# Pin-with-a-screen.net
KiCad netlist of a schematic drawn in EAGLE
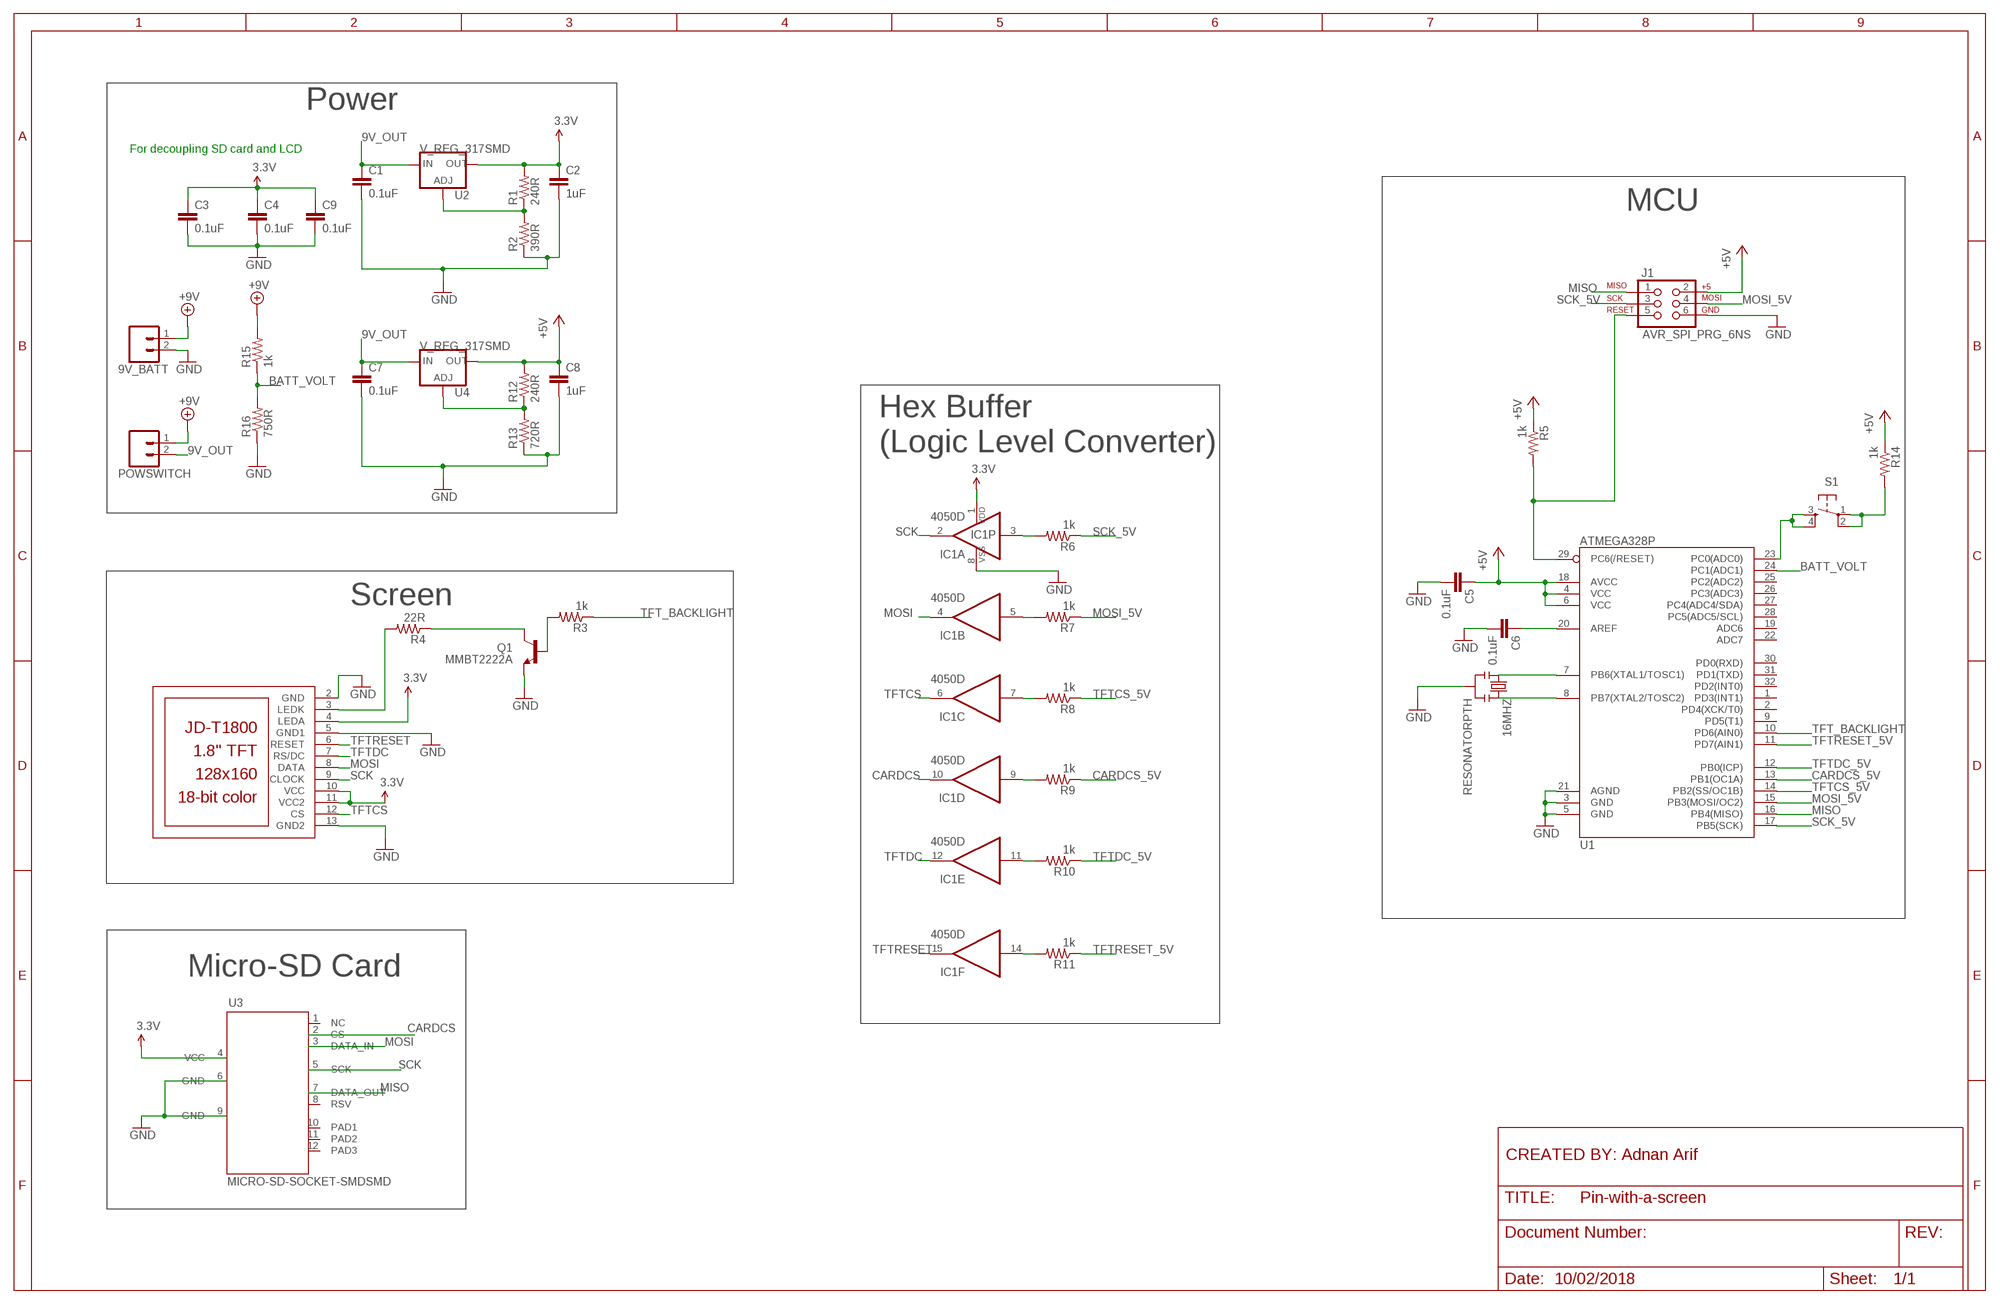
[diagram p0: schematic, sheet 1]

(export (version "E")
  (design (tool "Eeschema 10.0.6"))
  (components
    (comp (ref "9V_BATT")
      (value "M02POGO_PIN_HOLES_ONLY")
      (footprint "eagle-import:1X02_PP_HOLES_ONLY")
      (libsource (lib "eagle-import") (part "M02POGO_PIN_HOLES_ONLY"))
    )
    (comp (ref "16MHZ")
      (value "RESONATORPTH")
      (footprint "eagle-import:RESONATOR-PTH")
      (libsource (lib "eagle-import") (part "RESONATORPTH"))
    )
    (comp (ref "C1")
      (value "0.1uF")
      (footprint "eagle-import:0603-CAP")
      (libsource (lib "eagle-import") (part "CAP0603-CAP"))
    )
    (comp (ref "C2")
      (value "1uF")
      (footprint "eagle-import:0603-CAP")
      (libsource (lib "eagle-import") (part "CAP0603-CAP"))
    )
    (comp (ref "C3")
      (value "0.1uF")
      (footprint "eagle-import:0603-CAP")
      (libsource (lib "eagle-import") (part "CAP0603-CAP"))
    )
    (comp (ref "C4")
      (value "0.1uF")
      (footprint "eagle-import:0603-CAP")
      (libsource (lib "eagle-import") (part "CAP0603-CAP"))
    )
    (comp (ref "C5")
      (value "0.1uF")
      (footprint "eagle-import:0603-CAP")
      (libsource (lib "eagle-import") (part "CAP0603-CAP"))
    )
    (comp (ref "C6")
      (value "0.1uF")
      (footprint "eagle-import:0603-CAP")
      (libsource (lib "eagle-import") (part "CAP0603-CAP"))
    )
    (comp (ref "C7")
      (value "0.1uF")
      (footprint "eagle-import:0603-CAP")
      (libsource (lib "eagle-import") (part "CAP0603-CAP"))
    )
    (comp (ref "C8")
      (value "1uF")
      (footprint "eagle-import:0603-CAP")
      (libsource (lib "eagle-import") (part "CAP0603-CAP"))
    )
    (comp (ref "C9")
      (value "0.1uF")
      (footprint "eagle-import:0603-CAP")
      (libsource (lib "eagle-import") (part "CAP0603-CAP"))
    )
    (comp (ref "IC1")
      (value "4050D")
      (footprint "eagle-import:SO16")
      (libsource (lib "eagle-import") (part "4050D"))
    )
    (comp (ref "J1")
      (value "AVR_SPI_PRG_6NS")
      (footprint "eagle-import:2X3-NS")
      (libsource (lib "eagle-import") (part "AVR_SPI_PRG_6NS"))
    )
    (comp (ref "LCD2")
      (value "JD-T1800")
      (footprint "eagle-import:JD-T1800")
      (libsource (lib "eagle-import") (part "JD-T1800"))
    )
    (comp (ref "POWSWITCH")
      (value "M02POGO_PIN_HOLES_ONLY")
      (footprint "eagle-import:1X02_PP_HOLES_ONLY")
      (libsource (lib "eagle-import") (part "M02POGO_PIN_HOLES_ONLY"))
    )
    (comp (ref "Q1")
      (value "MMBT2222A")
      (footprint "eagle-import:SOT23-3")
      (libsource (lib "eagle-import") (part "TRANSISTOR_NPNMMBT2222A"))
    )
    (comp (ref "R1")
      (value "240R")
      (footprint "eagle-import:0603-RES")
      (libsource (lib "eagle-import") (part "RESISTOR0603-RES"))
    )
    (comp (ref "R2")
      (value "390R")
      (footprint "eagle-import:0603-RES")
      (libsource (lib "eagle-import") (part "RESISTOR0603-RES"))
    )
    (comp (ref "R3")
      (value "1k")
      (footprint "eagle-import:0603-RES")
      (libsource (lib "eagle-import") (part "RESISTOR0603-RES"))
    )
    (comp (ref "R4")
      (value "22R")
      (footprint "eagle-import:0603-RES")
      (libsource (lib "eagle-import") (part "RESISTOR0603-RES"))
    )
    (comp (ref "R5")
      (value "1k")
      (footprint "eagle-import:0603-RES")
      (libsource (lib "eagle-import") (part "RESISTOR0603-RES"))
    )
    (comp (ref "R6")
      (value "1k")
      (footprint "eagle-import:0603-RES")
      (libsource (lib "eagle-import") (part "RESISTOR0603-RES"))
    )
    (comp (ref "R7")
      (value "1k")
      (footprint "eagle-import:0603-RES")
      (libsource (lib "eagle-import") (part "RESISTOR0603-RES"))
    )
    (comp (ref "R8")
      (value "1k")
      (footprint "eagle-import:0603-RES")
      (libsource (lib "eagle-import") (part "RESISTOR0603-RES"))
    )
    (comp (ref "R9")
      (value "1k")
      (footprint "eagle-import:0603-RES")
      (libsource (lib "eagle-import") (part "RESISTOR0603-RES"))
    )
    (comp (ref "R10")
      (value "1k")
      (footprint "eagle-import:0603-RES")
      (libsource (lib "eagle-import") (part "RESISTOR0603-RES"))
    )
    (comp (ref "R11")
      (value "1k")
      (footprint "eagle-import:0603-RES")
      (libsource (lib "eagle-import") (part "RESISTOR0603-RES"))
    )
    (comp (ref "R12")
      (value "240R")
      (footprint "eagle-import:0603-RES")
      (libsource (lib "eagle-import") (part "RESISTOR0603-RES"))
    )
    (comp (ref "R13")
      (value "720R")
      (footprint "eagle-import:0603-RES")
      (libsource (lib "eagle-import") (part "RESISTOR0603-RES"))
    )
    (comp (ref "R14")
      (value "1k")
      (footprint "eagle-import:0603-RES")
      (libsource (lib "eagle-import") (part "RESISTOR0603-RES"))
    )
    (comp (ref "R15")
      (value "1k")
      (footprint "eagle-import:0603-RES")
      (libsource (lib "eagle-import") (part "RESISTOR0603-RES"))
    )
    (comp (ref "R16")
      (value "750R")
      (footprint "eagle-import:0603-RES")
      (libsource (lib "eagle-import") (part "RESISTOR0603-RES"))
    )
    (comp (ref "S1")
      (value "TAC_SWITCHPTH")
      (footprint "eagle-import:TACTILE-PTH")
      (libsource (lib "eagle-import") (part "TAC_SWITCHPTH"))
    )
    (comp (ref "U1")
      (value "ATMEGA328P")
      (footprint "eagle-import:TQFP32-08")
      (libsource (lib "eagle-import") (part "ATMEGA328_SMT"))
    )
    (comp (ref "U2")
      (value "V_REG_317SMD")
      (footprint "eagle-import:SOT223")
      (libsource (lib "eagle-import") (part "V_REG_317SMD"))
    )
    (comp (ref "U3")
      (value "MICRO-SD-SOCKET-SMDSMD")
      (footprint "eagle-import:MICRO-SD-SOCKET-SMD")
      (libsource (lib "eagle-import") (part "MICRO-SD-SOCKET-SMDSMD"))
    )
    (comp (ref "U4")
      (value "V_REG_317SMD")
      (footprint "eagle-import:SOT223")
      (libsource (lib "eagle-import") (part "V_REG_317SMD"))
    )
  )
  (nets
    (net (code "1") (name "+5V") (class "Default")
      (node (ref "C5") (pin "1") (pinfunction "1_1") (pintype "passive"))
      (node (ref "C8") (pin "1") (pinfunction "1_1") (pintype "passive"))
      (node (ref "J1") (pin "2") (pinfunction "2_2") (pintype "passive"))
      (node (ref "R12") (pin "2") (pinfunction "2_2") (pintype "passive"))
      (node (ref "R14") (pin "1") (pinfunction "1_1") (pintype "passive"))
      (node (ref "R5") (pin "1") (pinfunction "1_1") (pintype "passive"))
      (node (ref "U1") (pin "18") (pinfunction "AVCC_18") (pintype "bidirectional"))
      (node (ref "U1") (pin "4") (pinfunction "VCC_4") (pintype "bidirectional"))
      (node (ref "U1") (pin "6") (pinfunction "VCC_6") (pintype "bidirectional"))
      (node (ref "U4") (pin "2") (pinfunction "OUT_2") (pintype "output"))
    )
    (net (code "2") (name "+9V") (class "Default")
      (node (ref "9V_BATT") (pin "1") (pinfunction "1_1") (pintype "passive"))
      (node (ref "POWSWITCH") (pin "1") (pinfunction "1_1") (pintype "passive"))
      (node (ref "R15") (pin "2") (pinfunction "2_2") (pintype "passive"))
    )
    (net (code "3") (name "/9V_OUT") (class "Default")
      (node (ref "C1") (pin "1") (pinfunction "1_1") (pintype "passive"))
      (node (ref "C7") (pin "1") (pinfunction "1_1") (pintype "passive"))
      (node (ref "POWSWITCH") (pin "2") (pinfunction "2_2") (pintype "passive"))
      (node (ref "U2") (pin "3") (pinfunction "IN_3") (pintype "input"))
      (node (ref "U4") (pin "3") (pinfunction "IN_3") (pintype "input"))
    )
    (net (code "4") (name "/BATT_VOLT") (class "Default")
      (node (ref "R15") (pin "1") (pinfunction "1_1") (pintype "passive"))
      (node (ref "R16") (pin "2") (pinfunction "2_2") (pintype "passive"))
      (node (ref "U1") (pin "24") (pinfunction "PC1(ADC1)_24") (pintype "bidirectional"))
    )
    (net (code "5") (name "/CARDCS") (class "Default")
      (node (ref "IC1") (pin "10") (pinfunction "O_10") (pintype "output"))
      (node (ref "U3") (pin "2") (pinfunction "CS_2") (pintype "input"))
    )
    (net (code "6") (name "/CARDCS_5V") (class "Default")
      (node (ref "R9") (pin "1") (pinfunction "1_1") (pintype "passive"))
      (node (ref "U1") (pin "13") (pinfunction "PB1(OC1A)_13") (pintype "bidirectional"))
    )
    (net (code "7") (name "/MISO") (class "Default")
      (node (ref "J1") (pin "1") (pinfunction "1_1") (pintype "passive"))
      (node (ref "U1") (pin "16") (pinfunction "PB4(MISO)_16") (pintype "bidirectional"))
      (node (ref "U3") (pin "7") (pinfunction "DATA_OUT_7") (pintype "output"))
    )
    (net (code "8") (name "/MOSI") (class "Default")
      (node (ref "IC1") (pin "4") (pinfunction "O_4") (pintype "output"))
      (node (ref "LCD2") (pin "8") (pinfunction "DATA_8") (pintype "bidirectional"))
      (node (ref "U3") (pin "3") (pinfunction "DATA_IN_3") (pintype "input"))
    )
    (net (code "9") (name "/MOSI_5V") (class "Default")
      (node (ref "J1") (pin "4") (pinfunction "4_4") (pintype "passive"))
      (node (ref "R7") (pin "1") (pinfunction "1_1") (pintype "passive"))
      (node (ref "U1") (pin "15") (pinfunction "PB3(MOSI/OC2)_15") (pintype "bidirectional"))
    )
    (net (code "10") (name "/SCK") (class "Default")
      (node (ref "IC1") (pin "2") (pinfunction "O_2") (pintype "output"))
      (node (ref "LCD2") (pin "9") (pinfunction "CLOCK_9") (pintype "input"))
      (node (ref "U3") (pin "5") (pinfunction "SCK_5") (pintype "input"))
    )
    (net (code "11") (name "/SCK_5V") (class "Default")
      (node (ref "J1") (pin "3") (pinfunction "3_3") (pintype "passive"))
      (node (ref "R6") (pin "1") (pinfunction "1_1") (pintype "passive"))
      (node (ref "U1") (pin "17") (pinfunction "PB5(SCK)_17") (pintype "bidirectional"))
    )
    (net (code "12") (name "/TFTCS") (class "Default")
      (node (ref "IC1") (pin "6") (pinfunction "O_6") (pintype "output"))
      (node (ref "LCD2") (pin "12") (pinfunction "CS_12") (pintype "input"))
    )
    (net (code "13") (name "/TFTCS_5V") (class "Default")
      (node (ref "R8") (pin "1") (pinfunction "1_1") (pintype "passive"))
      (node (ref "U1") (pin "14") (pinfunction "PB2(SS/OC1B)_14") (pintype "bidirectional"))
    )
    (net (code "14") (name "/TFTDC") (class "Default")
      (node (ref "IC1") (pin "12") (pinfunction "O_12") (pintype "output"))
      (node (ref "LCD2") (pin "7") (pinfunction "RS/DC_7") (pintype "input"))
    )
    (net (code "15") (name "/TFTDC_5V") (class "Default")
      (node (ref "R10") (pin "1") (pinfunction "1_1") (pintype "passive"))
      (node (ref "U1") (pin "12") (pinfunction "PB0(ICP)_12") (pintype "bidirectional"))
    )
    (net (code "16") (name "/TFTRESET") (class "Default")
      (node (ref "IC1") (pin "15") (pinfunction "O_15") (pintype "output"))
      (node (ref "LCD2") (pin "6") (pinfunction "RESET_6") (pintype "input"))
    )
    (net (code "17") (name "/TFTRESET_5V") (class "Default")
      (node (ref "R11") (pin "1") (pinfunction "1_1") (pintype "passive"))
      (node (ref "U1") (pin "11") (pinfunction "PD7(AIN1)_11") (pintype "bidirectional"))
    )
    (net (code "18") (name "/TFT_BACKLIGHT") (class "Default")
      (node (ref "R3") (pin "1") (pinfunction "1_1") (pintype "passive"))
      (node (ref "U1") (pin "10") (pinfunction "PD6(AIN0)_10") (pintype "bidirectional"))
    )
    (net (code "19") (name "3.3V") (class "Default")
      (node (ref "C2") (pin "1") (pinfunction "1_1") (pintype "passive"))
      (node (ref "C3") (pin "1") (pinfunction "1_1") (pintype "passive"))
      (node (ref "C4") (pin "1") (pinfunction "1_1") (pintype "passive"))
      (node (ref "C9") (pin "1") (pinfunction "1_1") (pintype "passive"))
      (node (ref "IC1") (pin "1") (pinfunction "VDD_1") (pintype "power_in"))
      (node (ref "LCD2") (pin "10") (pinfunction "VCC_10") (pintype "power_in"))
      (node (ref "LCD2") (pin "11") (pinfunction "VCC2_11") (pintype "power_in"))
      (node (ref "LCD2") (pin "4") (pinfunction "LEDA_4") (pintype "input"))
      (node (ref "R1") (pin "2") (pinfunction "2_2") (pintype "passive"))
      (node (ref "U2") (pin "2") (pinfunction "OUT_2") (pintype "output"))
      (node (ref "U3") (pin "4") (pinfunction "VCC_4") (pintype "power_in"))
    )
    (net (code "20") (name "GND") (class "Default")
      (node (ref "16MHZ") (pin "2") (pinfunction "2_2") (pintype "passive"))
      (node (ref "9V_BATT") (pin "2") (pinfunction "2_2") (pintype "passive"))
      (node (ref "C1") (pin "2") (pinfunction "2_2") (pintype "passive"))
      (node (ref "C2") (pin "2") (pinfunction "2_2") (pintype "passive"))
      (node (ref "C3") (pin "2") (pinfunction "2_2") (pintype "passive"))
      (node (ref "C4") (pin "2") (pinfunction "2_2") (pintype "passive"))
      (node (ref "C5") (pin "2") (pinfunction "2_2") (pintype "passive"))
      (node (ref "C6") (pin "2") (pinfunction "2_2") (pintype "passive"))
      (node (ref "C7") (pin "2") (pinfunction "2_2") (pintype "passive"))
      (node (ref "C8") (pin "2") (pinfunction "2_2") (pintype "passive"))
      (node (ref "C9") (pin "2") (pinfunction "2_2") (pintype "passive"))
      (node (ref "IC1") (pin "8") (pinfunction "VSS_8") (pintype "power_in"))
      (node (ref "J1") (pin "6") (pinfunction "6_6") (pintype "passive"))
      (node (ref "LCD2") (pin "13") (pinfunction "GND2_13") (pintype "power_in"))
      (node (ref "LCD2") (pin "2") (pinfunction "GND_2") (pintype "power_in"))
      (node (ref "LCD2") (pin "5") (pinfunction "GND1_5") (pintype "power_in"))
      (node (ref "Q1") (pin "2") (pinfunction "E_2") (pintype "passive"))
      (node (ref "R13") (pin "1") (pinfunction "1_1") (pintype "passive"))
      (node (ref "R16") (pin "1") (pinfunction "1_1") (pintype "passive"))
      (node (ref "R2") (pin "1") (pinfunction "1_1") (pintype "passive"))
      (node (ref "U1") (pin "21") (pinfunction "AGND_21") (pintype "bidirectional"))
      (node (ref "U1") (pin "3") (pinfunction "GND_3") (pintype "bidirectional"))
      (node (ref "U1") (pin "5") (pinfunction "GND_5") (pintype "bidirectional"))
      (node (ref "U3") (pin "6") (pinfunction "GND_6") (pintype "power_in"))
      (node (ref "U3") (pin "9") (pinfunction "GND_9") (pintype "power_in"))
    )
    (net (code "21") (name "Net-(IC1A-I)") (class "Default")
      (node (ref "IC1") (pin "3") (pinfunction "I_3") (pintype "input"))
      (node (ref "R6") (pin "2") (pinfunction "2_2") (pintype "passive"))
    )
    (net (code "22") (name "Net-(IC1B-I)") (class "Default")
      (node (ref "IC1") (pin "5") (pinfunction "I_5") (pintype "input"))
      (node (ref "R7") (pin "2") (pinfunction "2_2") (pintype "passive"))
    )
    (net (code "23") (name "Net-(IC1C-I)") (class "Default")
      (node (ref "IC1") (pin "7") (pinfunction "I_7") (pintype "input"))
      (node (ref "R8") (pin "2") (pinfunction "2_2") (pintype "passive"))
    )
    (net (code "24") (name "Net-(IC1D-I)") (class "Default")
      (node (ref "IC1") (pin "9") (pinfunction "I_9") (pintype "input"))
      (node (ref "R9") (pin "2") (pinfunction "2_2") (pintype "passive"))
    )
    (net (code "25") (name "Net-(IC1E-I)") (class "Default")
      (node (ref "IC1") (pin "11") (pinfunction "I_11") (pintype "input"))
      (node (ref "R10") (pin "2") (pinfunction "2_2") (pintype "passive"))
    )
    (net (code "26") (name "Net-(IC1F-I)") (class "Default")
      (node (ref "IC1") (pin "14") (pinfunction "I_14") (pintype "input"))
      (node (ref "R11") (pin "2") (pinfunction "2_2") (pintype "passive"))
    )
    (net (code "27") (name "Net-(LCD2-LEDK)") (class "Default")
      (node (ref "LCD2") (pin "3") (pinfunction "LEDK_3") (pintype "input"))
      (node (ref "R4") (pin "2") (pinfunction "2_2") (pintype "passive"))
    )
    (net (code "28") (name "Net-(Q1-B)") (class "Default")
      (node (ref "Q1") (pin "1") (pinfunction "B_1") (pintype "passive"))
      (node (ref "R3") (pin "2") (pinfunction "2_2") (pintype "passive"))
    )
    (net (code "29") (name "Net-(Q1-C)") (class "Default")
      (node (ref "Q1") (pin "3") (pinfunction "C_3") (pintype "passive"))
      (node (ref "R4") (pin "1") (pinfunction "1_1") (pintype "passive"))
    )
    (net (code "30") (name "Net-(R14-Pad2)") (class "Default")
      (node (ref "R14") (pin "2") (pinfunction "2_2") (pintype "passive"))
      (node (ref "S1") (pin "1") (pinfunction "1_1") (pintype "passive"))
      (node (ref "S1") (pin "2") (pinfunction "2_2") (pintype "passive"))
    )
    (net (code "31") (name "Net-(U1-AREF)") (class "Default")
      (node (ref "C6") (pin "1") (pinfunction "1_1") (pintype "passive"))
      (node (ref "U1") (pin "20") (pinfunction "AREF_20") (pintype "bidirectional"))
    )
    (net (code "32") (name "Net-(U1-PB6(XTAL1{slash}TOSC1))") (class "Default")
      (node (ref "16MHZ") (pin "1") (pinfunction "1_1") (pintype "passive"))
      (node (ref "U1") (pin "7") (pinfunction "PB6(XTAL1/TOSC1)_7") (pintype "bidirectional"))
    )
    (net (code "33") (name "Net-(U1-PB7(XTAL2{slash}TOSC2))") (class "Default")
      (node (ref "16MHZ") (pin "3") (pinfunction "3_3") (pintype "passive"))
      (node (ref "U1") (pin "8") (pinfunction "PB7(XTAL2/TOSC2)_8") (pintype "bidirectional"))
    )
    (net (code "34") (name "Net-(U1-PC0(ADC0))") (class "Default")
      (node (ref "S1") (pin "3") (pinfunction "3_3") (pintype "passive"))
      (node (ref "S1") (pin "4") (pinfunction "4_4") (pintype "passive"))
      (node (ref "U1") (pin "23") (pinfunction "PC0(ADC0)_23") (pintype "bidirectional"))
    )
    (net (code "35") (name "Net-(U1-PC6({slash}RESET))") (class "Default")
      (node (ref "J1") (pin "5") (pinfunction "5_5") (pintype "passive"))
      (node (ref "R5") (pin "2") (pinfunction "2_2") (pintype "passive"))
      (node (ref "U1") (pin "29") (pinfunction "PC6(/RESET)_29") (pintype "bidirectional"))
    )
    (net (code "36") (name "Net-(U2-ADJ)") (class "Default")
      (node (ref "R1") (pin "1") (pinfunction "1_1") (pintype "passive"))
      (node (ref "R2") (pin "2") (pinfunction "2_2") (pintype "passive"))
      (node (ref "U2") (pin "1") (pinfunction "ADJ_1") (pintype "input"))
    )
    (net (code "37") (name "Net-(U4-ADJ)") (class "Default")
      (node (ref "R12") (pin "1") (pinfunction "1_1") (pintype "passive"))
      (node (ref "R13") (pin "2") (pinfunction "2_2") (pintype "passive"))
      (node (ref "U4") (pin "1") (pinfunction "ADJ_1") (pintype "input"))
    )
    (net (code "38") (name "unconnected-(U1-ADC6-Pad19)") (class "Default")
      (node (ref "U1") (pin "19") (pinfunction "ADC6_19") (pintype "bidirectional"))
    )
    (net (code "39") (name "unconnected-(U1-ADC7-Pad22)") (class "Default")
      (node (ref "U1") (pin "22") (pinfunction "ADC7_22") (pintype "bidirectional"))
    )
    (net (code "40") (name "unconnected-(U1-PC2(ADC2)-Pad25)") (class "Default")
      (node (ref "U1") (pin "25") (pinfunction "PC2(ADC2)_25") (pintype "bidirectional"))
    )
    (net (code "41") (name "unconnected-(U1-PC3(ADC3)-Pad26)") (class "Default")
      (node (ref "U1") (pin "26") (pinfunction "PC3(ADC3)_26") (pintype "bidirectional"))
    )
    (net (code "42") (name "unconnected-(U1-PC4(ADC4{slash}SDA)-Pad27)") (class "Default")
      (node (ref "U1") (pin "27") (pinfunction "PC4(ADC4/SDA)_27") (pintype "bidirectional"))
    )
    (net (code "43") (name "unconnected-(U1-PC5(ADC5{slash}SCL)-Pad28)") (class "Default")
      (node (ref "U1") (pin "28") (pinfunction "PC5(ADC5/SCL)_28") (pintype "bidirectional"))
    )
    (net (code "44") (name "unconnected-(U1-PD0(RXD)-Pad30)") (class "Default")
      (node (ref "U1") (pin "30") (pinfunction "PD0(RXD)_30") (pintype "bidirectional"))
    )
    (net (code "45") (name "unconnected-(U1-PD1(TXD)-Pad31)") (class "Default")
      (node (ref "U1") (pin "31") (pinfunction "PD1(TXD)_31") (pintype "bidirectional"))
    )
    (net (code "46") (name "unconnected-(U1-PD2(INT0)-Pad32)") (class "Default")
      (node (ref "U1") (pin "32") (pinfunction "PD2(INT0)_32") (pintype "bidirectional"))
    )
    (net (code "47") (name "unconnected-(U1-PD3(INT1)-Pad1)") (class "Default")
      (node (ref "U1") (pin "1") (pinfunction "PD3(INT1)_1") (pintype "bidirectional"))
    )
    (net (code "48") (name "unconnected-(U1-PD4(XCK{slash}T0)-Pad2)") (class "Default")
      (node (ref "U1") (pin "2") (pinfunction "PD4(XCK/T0)_2") (pintype "bidirectional"))
    )
    (net (code "49") (name "unconnected-(U1-PD5(T1)-Pad9)") (class "Default")
      (node (ref "U1") (pin "9") (pinfunction "PD5(T1)_9") (pintype "bidirectional"))
    )
    (net (code "50") (name "unconnected-(U3-NC-Pad1)") (class "Default")
      (node (ref "U3") (pin "1") (pinfunction "NC_1") (pintype "no_connect"))
    )
    (net (code "51") (name "unconnected-(U3-PAD1-Pad10)") (class "Default")
      (node (ref "U3") (pin "10") (pinfunction "PAD1_10") (pintype "bidirectional"))
    )
    (net (code "52") (name "unconnected-(U3-PAD2-Pad11)") (class "Default")
      (node (ref "U3") (pin "11") (pinfunction "PAD2_11") (pintype "bidirectional"))
    )
    (net (code "53") (name "unconnected-(U3-PAD3-Pad12)") (class "Default")
      (node (ref "U3") (pin "12") (pinfunction "PAD3_12") (pintype "bidirectional"))
    )
    (net (code "54") (name "unconnected-(U3-RSV-Pad8)") (class "Default")
      (node (ref "U3") (pin "8") (pinfunction "RSV_8") (pintype "bidirectional"))
    )
  )
)
